# positioningAndThermistor.net
KiCad netlist of a schematic drawn in Altium Designer
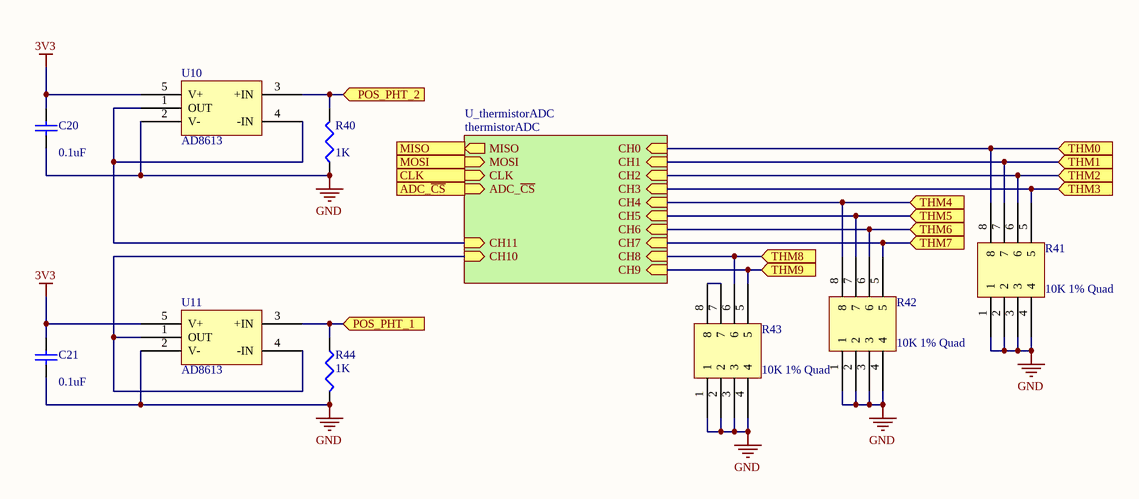
[diagram p0: positioningAndThermistor.SchDoc]

(export (version "E")
  (design (tool "Eeschema 10.0.6"))
  (components
    (comp (ref "C20")
      (value "0.1uF")
      (footprint "1608[0603]")
      (description "Capacitor (Semiconductor SIM Model)")
      (fields (field (name "PUBLISHER") "Altium Limited"))
      (libsource (lib "Miscellaneous Devices") (part "Cap Semi"))
    )
    (comp (ref "C21")
      (value "0.1uF")
      (footprint "1608[0603]")
      (description "Capacitor (Semiconductor SIM Model)")
      (fields (field (name "PUBLISHER") "Altium Limited"))
      (libsource (lib "Miscellaneous Devices") (part "Cap Semi"))
    )
    (comp (ref "R40")
      (value "1K")
      (footprint "J1-0603")
      (description "Resistor")
      (fields (field (name "PUBLISHER") "Altium Limited"))
      (libsource (lib "Miscellaneous Devices") (part "Res3"))
    )
    (comp (ref "R41")
      (value "10K 1% Quad")
      (footprint "ResQuad-320X150")
      (description "Quad pack resistor")
      (libsource (lib "PAY") (part "Res Quad Pack"))
    )
    (comp (ref "R42")
      (value "10K 1% Quad")
      (footprint "ResQuad-320X150")
      (description "Quad pack resistor")
      (libsource (lib "PAY") (part "Res Quad Pack"))
    )
    (comp (ref "R43")
      (value "10K 1% Quad")
      (footprint "ResQuad-320X150")
      (description "Quad pack resistor")
      (libsource (lib "PAY") (part "Res Quad Pack"))
    )
    (comp (ref "R44")
      (value "1K")
      (footprint "J1-0603")
      (description "Resistor")
      (fields (field (name "PUBLISHER") "Altium Limited"))
      (libsource (lib "Miscellaneous Devices") (part "Res3"))
    )
    (comp (ref "U10")
      (value "AD8613")
      (footprint "SOP-65P200X125-5N")
      (description "Low power, low noise rail-to-rail op-amp.")
      (libsource (lib "PAY") (part "AD8613"))
    )
    (comp (ref "U11")
      (value "AD8613")
      (footprint "SOP-65P200X125-5N")
      (description "Low power, low noise rail-to-rail op-amp.")
      (libsource (lib "PAY") (part "AD8613"))
    )
  )
  (nets
    (net (code "2") (name "/CH10") (class "Default")
      (node (ref "U11") (pin "1") (pinfunction "OUT_1") (pintype "passive"))
      (node (ref "U11") (pin "4") (pinfunction "-IN_4") (pintype "passive"))
    )
    (net (code "3") (name "/CH11") (class "Default")
      (node (ref "U10") (pin "1") (pinfunction "OUT_1") (pintype "passive"))
      (node (ref "U10") (pin "4") (pinfunction "-IN_4") (pintype "passive"))
    )
    (net (code "7") (name "/POS_PHT_1") (class "Default")
      (node (ref "R44") (pin "1") (pinfunction "1_1") (pintype "passive"))
      (node (ref "U11") (pin "3") (pinfunction "+IN_3") (pintype "passive"))
    )
    (net (code "8") (name "/POS_PHT_2") (class "Default")
      (node (ref "R40") (pin "2") (pinfunction "2_2") (pintype "passive"))
      (node (ref "U10") (pin "3") (pinfunction "+IN_3") (pintype "passive"))
    )
    (net (code "9") (name "/THM0") (class "Default")
      (node (ref "R41") (pin "8") (pinfunction "8_8") (pintype "passive"))
    )
    (net (code "10") (name "/THM1") (class "Default")
      (node (ref "R41") (pin "7") (pinfunction "7_7") (pintype "passive"))
    )
    (net (code "11") (name "/THM2") (class "Default")
      (node (ref "R41") (pin "6") (pinfunction "6_6") (pintype "passive"))
    )
    (net (code "12") (name "/THM3") (class "Default")
      (node (ref "R41") (pin "5") (pinfunction "5_5") (pintype "passive"))
    )
    (net (code "13") (name "/THM4") (class "Default")
      (node (ref "R42") (pin "8") (pinfunction "8_8") (pintype "passive"))
    )
    (net (code "14") (name "/THM5") (class "Default")
      (node (ref "R42") (pin "7") (pinfunction "7_7") (pintype "passive"))
    )
    (net (code "15") (name "/THM6") (class "Default")
      (node (ref "R42") (pin "6") (pinfunction "6_6") (pintype "passive"))
    )
    (net (code "16") (name "/THM7") (class "Default")
      (node (ref "R42") (pin "5") (pinfunction "5_5") (pintype "passive"))
    )
    (net (code "17") (name "/THM8") (class "Default")
      (node (ref "R43") (pin "6") (pinfunction "6_6") (pintype "passive"))
    )
    (net (code "18") (name "/THM9") (class "Default")
      (node (ref "R43") (pin "5") (pinfunction "5_5") (pintype "passive"))
    )
    (net (code "19") (name "3V3") (class "Default")
      (node (ref "C20") (pin "2") (pinfunction "2_2") (pintype "passive"))
      (node (ref "C21") (pin "2") (pinfunction "2_2") (pintype "passive"))
      (node (ref "U10") (pin "5") (pinfunction "V+_5") (pintype "passive"))
      (node (ref "U11") (pin "5") (pinfunction "V+_5") (pintype "passive"))
    )
    (net (code "20") (name "GND") (class "Default")
      (node (ref "C20") (pin "1") (pinfunction "1_1") (pintype "passive"))
      (node (ref "C21") (pin "1") (pinfunction "1_1") (pintype "passive"))
      (node (ref "R40") (pin "1") (pinfunction "1_1") (pintype "passive"))
      (node (ref "R41") (pin "1") (pinfunction "1_1") (pintype "passive"))
      (node (ref "R41") (pin "2") (pinfunction "2_2") (pintype "passive"))
      (node (ref "R41") (pin "3") (pinfunction "3_3") (pintype "passive"))
      (node (ref "R41") (pin "4") (pinfunction "4_4") (pintype "passive"))
      (node (ref "R42") (pin "1") (pinfunction "1_1") (pintype "passive"))
      (node (ref "R42") (pin "2") (pinfunction "2_2") (pintype "passive"))
      (node (ref "R42") (pin "3") (pinfunction "3_3") (pintype "passive"))
      (node (ref "R42") (pin "4") (pinfunction "4_4") (pintype "passive"))
      (node (ref "R43") (pin "1") (pinfunction "1_1") (pintype "passive"))
      (node (ref "R43") (pin "2") (pinfunction "2_2") (pintype "passive"))
      (node (ref "R43") (pin "3") (pinfunction "3_3") (pintype "passive"))
      (node (ref "R43") (pin "4") (pinfunction "4_4") (pintype "passive"))
      (node (ref "R44") (pin "2") (pinfunction "2_2") (pintype "passive"))
      (node (ref "U10") (pin "2") (pinfunction "V-_2") (pintype "passive"))
      (node (ref "U11") (pin "2") (pinfunction "V-_2") (pintype "passive"))
    )
    (net (code "21") (name "Net-(R43-Pad7)") (class "Default")
      (node (ref "R43") (pin "7") (pinfunction "7_7") (pintype "passive"))
      (node (ref "R43") (pin "8") (pinfunction "8_8") (pintype "passive"))
    )
  )
)
